# word_clock.net
KiCad netlist of a schematic drawn in EAGLE
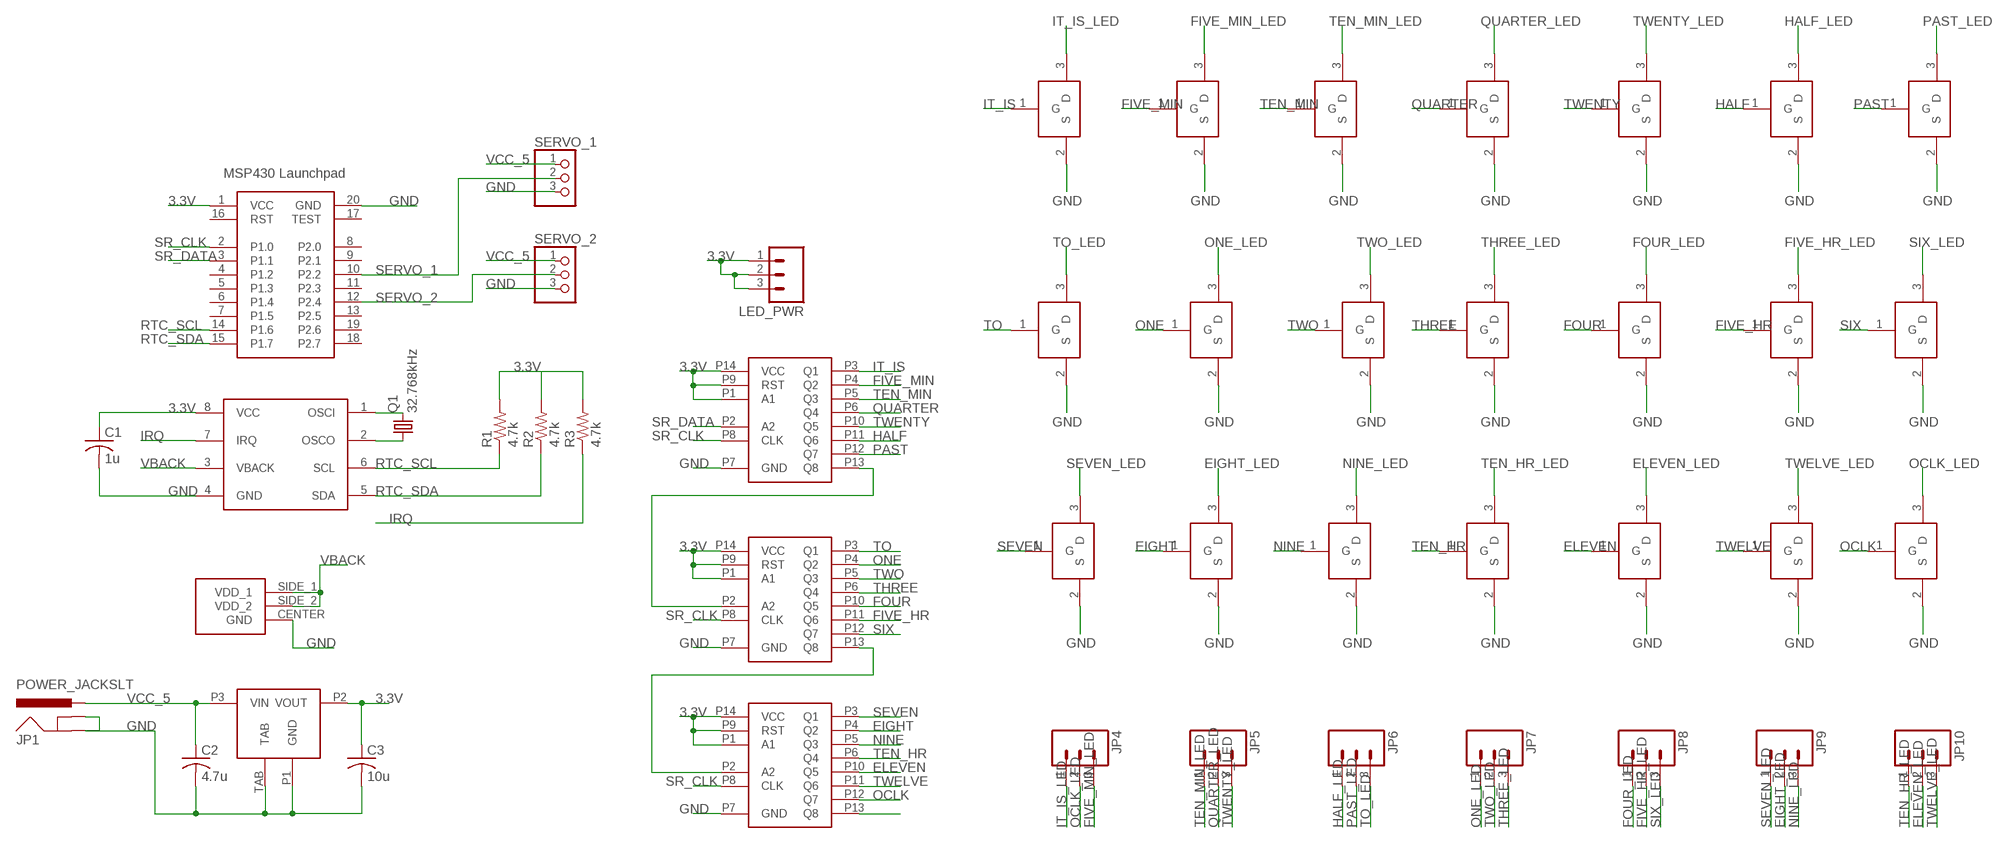
[diagram p0: schematic, sheet 1]

(export (version "E")
  (design (tool "Eeschema 10.0.6"))
  (components
    (comp (ref "1H")
      (value "FET")
      (footprint "eagle-import:SOT23")
      (libsource (lib "eagle-import") (part "FET"))
    )
    (comp (ref "2H")
      (value "FET")
      (footprint "eagle-import:SOT23")
      (libsource (lib "eagle-import") (part "FET"))
    )
    (comp (ref "3H")
      (value "FET")
      (footprint "eagle-import:SOT23")
      (libsource (lib "eagle-import") (part "FET"))
    )
    (comp (ref "4H")
      (value "FET")
      (footprint "eagle-import:SOT23")
      (libsource (lib "eagle-import") (part "FET"))
    )
    (comp (ref "5H")
      (value "FET")
      (footprint "eagle-import:SOT23")
      (libsource (lib "eagle-import") (part "FET"))
    )
    (comp (ref "5M")
      (value "FET")
      (footprint "eagle-import:SOT23")
      (libsource (lib "eagle-import") (part "FET"))
    )
    (comp (ref "6H")
      (value "FET")
      (footprint "eagle-import:SOT23")
      (libsource (lib "eagle-import") (part "FET"))
    )
    (comp (ref "7H")
      (value "FET")
      (footprint "eagle-import:SOT23")
      (libsource (lib "eagle-import") (part "FET"))
    )
    (comp (ref "8H")
      (value "FET")
      (footprint "eagle-import:SOT23")
      (libsource (lib "eagle-import") (part "FET"))
    )
    (comp (ref "9H")
      (value "FET")
      (footprint "eagle-import:SOT23")
      (libsource (lib "eagle-import") (part "FET"))
    )
    (comp (ref "10H")
      (value "FET")
      (footprint "eagle-import:SOT23")
      (libsource (lib "eagle-import") (part "FET"))
    )
    (comp (ref "10M")
      (value "FET")
      (footprint "eagle-import:SOT23")
      (libsource (lib "eagle-import") (part "FET"))
    )
    (comp (ref "11H")
      (value "FET")
      (footprint "eagle-import:SOT23")
      (libsource (lib "eagle-import") (part "FET"))
    )
    (comp (ref "12H")
      (value "FET")
      (footprint "eagle-import:SOT23")
      (libsource (lib "eagle-import") (part "FET"))
    )
    (comp (ref "15M")
      (value "FET")
      (footprint "eagle-import:SOT23")
      (libsource (lib "eagle-import") (part "FET"))
    )
    (comp (ref "20M")
      (value "FET")
      (footprint "eagle-import:SOT23")
      (libsource (lib "eagle-import") (part "FET"))
    )
    (comp (ref "30M")
      (value "FET")
      (footprint "eagle-import:SOT23")
      (libsource (lib "eagle-import") (part "FET"))
    )
    (comp (ref "C1")
      (value "1u")
      (footprint "eagle-import:C050-025X075")
      (libsource (lib "eagle-import") (part "C-US050-025X075"))
    )
    (comp (ref "C2")
      (value "4.7u")
      (footprint "eagle-import:C050-025X075")
      (libsource (lib "eagle-import") (part "C-US050-025X075"))
    )
    (comp (ref "C3")
      (value "10u")
      (footprint "eagle-import:C050-025X075")
      (libsource (lib "eagle-import") (part "C-US050-025X075"))
    )
    (comp (ref "ITIS")
      (value "FET")
      (footprint "eagle-import:SOT23")
      (libsource (lib "eagle-import") (part "FET"))
    )
    (comp (ref "JP1")
      (value "POWER_JACKSLT")
      (footprint "eagle-import:POWER_JACK_SLOT")
      (libsource (lib "eagle-import") (part "POWER_JACKSLT"))
    )
    (comp (ref "JP4")
      (value "M03-SCREW-5MM")
      (footprint "eagle-import:SCREWTERMINAL-5MM-3")
      (libsource (lib "eagle-import") (part "M03-SCREW-5MM"))
    )
    (comp (ref "JP5")
      (value "M03-SCREW-5MM")
      (footprint "eagle-import:SCREWTERMINAL-5MM-3")
      (libsource (lib "eagle-import") (part "M03-SCREW-5MM"))
    )
    (comp (ref "JP6")
      (value "M03-SCREW-5MM")
      (footprint "eagle-import:SCREWTERMINAL-5MM-3")
      (libsource (lib "eagle-import") (part "M03-SCREW-5MM"))
    )
    (comp (ref "JP7")
      (value "M03-SCREW-5MM")
      (footprint "eagle-import:SCREWTERMINAL-5MM-3")
      (libsource (lib "eagle-import") (part "M03-SCREW-5MM"))
    )
    (comp (ref "JP8")
      (value "M03-SCREW-5MM")
      (footprint "eagle-import:SCREWTERMINAL-5MM-3")
      (libsource (lib "eagle-import") (part "M03-SCREW-5MM"))
    )
    (comp (ref "JP9")
      (value "M03-SCREW-5MM")
      (footprint "eagle-import:SCREWTERMINAL-5MM-3")
      (libsource (lib "eagle-import") (part "M03-SCREW-5MM"))
    )
    (comp (ref "JP10")
      (value "M03-SCREW-5MM")
      (footprint "eagle-import:SCREWTERMINAL-5MM-3")
      (libsource (lib "eagle-import") (part "M03-SCREW-5MM"))
    )
    (comp (ref "LED_PWR")
      (value "M03-SCREW-5MM")
      (footprint "eagle-import:SCREWTERMINAL-5MM-3")
      (libsource (lib "eagle-import") (part "M03-SCREW-5MM"))
    )
    (comp (ref "OCLK")
      (value "FET")
      (footprint "eagle-import:SOT23")
      (libsource (lib "eagle-import") (part "FET"))
    )
    (comp (ref "PAST")
      (value "FET")
      (footprint "eagle-import:SOT23")
      (libsource (lib "eagle-import") (part "FET"))
    )
    (comp (ref "Q1")
      (value "32.768kHz")
      (footprint "eagle-import:TC26V")
      (libsource (lib "eagle-import") (part "CRYSTALTC26V"))
    )
    (comp (ref "R1")
      (value "4.7k")
      (footprint "eagle-import:0207_10")
      (libsource (lib "eagle-import") (part "R-US_0207/10"))
    )
    (comp (ref "R2")
      (value "4.7k")
      (footprint "eagle-import:0207_10")
      (libsource (lib "eagle-import") (part "R-US_0207/10"))
    )
    (comp (ref "R3")
      (value "4.7k")
      (footprint "eagle-import:0207_10")
      (libsource (lib "eagle-import") (part "R-US_0207/10"))
    )
    (comp (ref "RTC")
      (value "RTC")
      (footprint "eagle-import:SOIC8")
      (libsource (lib "eagle-import") (part "RTC"))
    )
    (comp (ref "SERVO_1")
      (value "PINHD-1X3")
      (footprint "eagle-import:1X03")
      (libsource (lib "eagle-import") (part "PINHD-1X3"))
    )
    (comp (ref "SERVO_2")
      (value "PINHD-1X3")
      (footprint "eagle-import:1X03")
      (libsource (lib "eagle-import") (part "PINHD-1X3"))
    )
    (comp (ref "SR_1")
      (value "SHIFT_REGISTER")
      (footprint "eagle-import:SHIFT_REGISTER")
      (libsource (lib "eagle-import") (part "SHIFT_REGISTER"))
    )
    (comp (ref "SR_2")
      (value "SHIFT_REGISTER")
      (footprint "eagle-import:SHIFT_REGISTER")
      (libsource (lib "eagle-import") (part "SHIFT_REGISTER"))
    )
    (comp (ref "TO")
      (value "FET")
      (footprint "eagle-import:SOT23")
      (libsource (lib "eagle-import") (part "FET"))
    )
    (comp (ref "U$1")
      (value "SHIFT_REGISTER")
      (footprint "eagle-import:SHIFT_REGISTER")
      (libsource (lib "eagle-import") (part "SHIFT_REGISTER"))
    )
    (comp (ref "U$4")
      (value "LDO")
      (footprint "eagle-import:LDO")
      (libsource (lib "eagle-import") (part "LDO"))
    )
    (comp (ref "U$25")
      (value "MSP430")
      (footprint "eagle-import:MSP430")
      (libsource (lib "eagle-import") (part "MSP430"))
    )
    (comp (ref "U$28")
      (value "COIN_CELL_SPARKFUN")
      (footprint "eagle-import:COIN_CELL_SPARKFUN")
      (libsource (lib "eagle-import") (part "COIN_CELL_SPARKFUN"))
    )
  )
  (nets
    (net (code "1") (name "/3.3V") (class "Default")
      (node (ref "C1") (pin "1") (pinfunction "1_1") (pintype "passive"))
      (node (ref "C3") (pin "1") (pinfunction "1_1") (pintype "passive"))
      (node (ref "LED_PWR") (pin "1") (pinfunction "1_1") (pintype "passive"))
      (node (ref "LED_PWR") (pin "2") (pinfunction "2_2") (pintype "passive"))
      (node (ref "LED_PWR") (pin "3") (pinfunction "3_3") (pintype "passive"))
      (node (ref "R1") (pin "2") (pinfunction "2_2") (pintype "passive"))
      (node (ref "R2") (pin "2") (pinfunction "2_2") (pintype "passive"))
      (node (ref "R3") (pin "2") (pinfunction "2_2") (pintype "passive"))
      (node (ref "RTC") (pin "8") (pinfunction "VCC_8") (pintype "bidirectional"))
      (node (ref "SR_1") (pin "P1") (pinfunction "A1_P1") (pintype "bidirectional"))
      (node (ref "SR_1") (pin "P14") (pinfunction "VCC_P14") (pintype "bidirectional"))
      (node (ref "SR_1") (pin "P9") (pinfunction "RST_P9") (pintype "bidirectional"))
      (node (ref "SR_2") (pin "P1") (pinfunction "A1_P1") (pintype "bidirectional"))
      (node (ref "SR_2") (pin "P14") (pinfunction "VCC_P14") (pintype "bidirectional"))
      (node (ref "SR_2") (pin "P9") (pinfunction "RST_P9") (pintype "bidirectional"))
      (node (ref "U$1") (pin "P1") (pinfunction "A1_P1") (pintype "bidirectional"))
      (node (ref "U$1") (pin "P14") (pinfunction "VCC_P14") (pintype "bidirectional"))
      (node (ref "U$1") (pin "P9") (pinfunction "RST_P9") (pintype "bidirectional"))
      (node (ref "U$25") (pin "1") (pinfunction "VCC_1") (pintype "bidirectional"))
      (node (ref "U$4") (pin "P2") (pinfunction "VOUT_P2") (pintype "bidirectional"))
    )
    (net (code "2") (name "/EIGHT") (class "Default")
      (node (ref "8H") (pin "1") (pinfunction "G_1") (pintype "bidirectional"))
      (node (ref "U$1") (pin "P4") (pinfunction "Q2_P4") (pintype "bidirectional"))
    )
    (net (code "3") (name "/EIGHT_LED") (class "Default")
      (node (ref "8H") (pin "3") (pinfunction "D_3") (pintype "bidirectional"))
      (node (ref "JP9") (pin "2") (pinfunction "2_2") (pintype "passive"))
    )
    (net (code "4") (name "/ELEVEN") (class "Default")
      (node (ref "11H") (pin "1") (pinfunction "G_1") (pintype "bidirectional"))
      (node (ref "U$1") (pin "P10") (pinfunction "Q5_P10") (pintype "bidirectional"))
    )
    (net (code "5") (name "/ELEVEN_LED") (class "Default")
      (node (ref "11H") (pin "3") (pinfunction "D_3") (pintype "bidirectional"))
      (node (ref "JP10") (pin "2") (pinfunction "2_2") (pintype "passive"))
    )
    (net (code "6") (name "/FIVE_HR") (class "Default")
      (node (ref "5H") (pin "1") (pinfunction "G_1") (pintype "bidirectional"))
      (node (ref "SR_2") (pin "P11") (pinfunction "Q6_P11") (pintype "bidirectional"))
    )
    (net (code "7") (name "/FIVE_HR_LED") (class "Default")
      (node (ref "5H") (pin "3") (pinfunction "D_3") (pintype "bidirectional"))
      (node (ref "JP8") (pin "2") (pinfunction "2_2") (pintype "passive"))
    )
    (net (code "8") (name "/FIVE_MIN") (class "Default")
      (node (ref "5M") (pin "1") (pinfunction "G_1") (pintype "bidirectional"))
      (node (ref "SR_1") (pin "P4") (pinfunction "Q2_P4") (pintype "bidirectional"))
    )
    (net (code "9") (name "/FIVE_MIN_LED") (class "Default")
      (node (ref "5M") (pin "3") (pinfunction "D_3") (pintype "bidirectional"))
      (node (ref "JP4") (pin "3") (pinfunction "3_3") (pintype "passive"))
    )
    (net (code "10") (name "/FOUR") (class "Default")
      (node (ref "4H") (pin "1") (pinfunction "G_1") (pintype "bidirectional"))
      (node (ref "SR_2") (pin "P10") (pinfunction "Q5_P10") (pintype "bidirectional"))
    )
    (net (code "11") (name "/FOUR_LED") (class "Default")
      (node (ref "4H") (pin "3") (pinfunction "D_3") (pintype "bidirectional"))
      (node (ref "JP8") (pin "1") (pinfunction "1_1") (pintype "passive"))
    )
    (net (code "12") (name "/GND") (class "Default")
      (node (ref "10H") (pin "2") (pinfunction "S_2") (pintype "bidirectional"))
      (node (ref "10M") (pin "2") (pinfunction "S_2") (pintype "bidirectional"))
      (node (ref "11H") (pin "2") (pinfunction "S_2") (pintype "bidirectional"))
      (node (ref "12H") (pin "2") (pinfunction "S_2") (pintype "bidirectional"))
      (node (ref "15M") (pin "2") (pinfunction "S_2") (pintype "bidirectional"))
      (node (ref "1H") (pin "2") (pinfunction "S_2") (pintype "bidirectional"))
      (node (ref "20M") (pin "2") (pinfunction "S_2") (pintype "bidirectional"))
      (node (ref "2H") (pin "2") (pinfunction "S_2") (pintype "bidirectional"))
      (node (ref "30M") (pin "2") (pinfunction "S_2") (pintype "bidirectional"))
      (node (ref "3H") (pin "2") (pinfunction "S_2") (pintype "bidirectional"))
      (node (ref "4H") (pin "2") (pinfunction "S_2") (pintype "bidirectional"))
      (node (ref "5H") (pin "2") (pinfunction "S_2") (pintype "bidirectional"))
      (node (ref "5M") (pin "2") (pinfunction "S_2") (pintype "bidirectional"))
      (node (ref "6H") (pin "2") (pinfunction "S_2") (pintype "bidirectional"))
      (node (ref "7H") (pin "2") (pinfunction "S_2") (pintype "bidirectional"))
      (node (ref "8H") (pin "2") (pinfunction "S_2") (pintype "bidirectional"))
      (node (ref "9H") (pin "2") (pinfunction "S_2") (pintype "bidirectional"))
      (node (ref "C1") (pin "2") (pinfunction "2_2") (pintype "passive"))
      (node (ref "C2") (pin "2") (pinfunction "2_2") (pintype "passive"))
      (node (ref "C3") (pin "2") (pinfunction "2_2") (pintype "passive"))
      (node (ref "ITIS") (pin "2") (pinfunction "S_2") (pintype "bidirectional"))
      (node (ref "JP1") (pin "GND@1") (pinfunction "GNDBREAK_GND@1") (pintype "bidirectional"))
      (node (ref "JP1") (pin "GND@2") (pinfunction "GND_GND@2") (pintype "bidirectional"))
      (node (ref "OCLK") (pin "2") (pinfunction "S_2") (pintype "bidirectional"))
      (node (ref "PAST") (pin "2") (pinfunction "S_2") (pintype "bidirectional"))
      (node (ref "RTC") (pin "4") (pinfunction "GND_4") (pintype "bidirectional"))
      (node (ref "SERVO_1") (pin "3") (pinfunction "3_3") (pintype "passive"))
      (node (ref "SERVO_2") (pin "3") (pinfunction "3_3") (pintype "passive"))
      (node (ref "SR_1") (pin "P7") (pinfunction "GND_P7") (pintype "bidirectional"))
      (node (ref "SR_2") (pin "P7") (pinfunction "GND_P7") (pintype "bidirectional"))
      (node (ref "TO") (pin "2") (pinfunction "S_2") (pintype "bidirectional"))
      (node (ref "U$1") (pin "P7") (pinfunction "GND_P7") (pintype "bidirectional"))
      (node (ref "U$25") (pin "20") (pinfunction "GND_20") (pintype "bidirectional"))
      (node (ref "U$28") (pin "CENTER") (pinfunction "GND_CENTER") (pintype "bidirectional"))
      (node (ref "U$4") (pin "P1") (pinfunction "GND_P1") (pintype "bidirectional"))
      (node (ref "U$4") (pin "TAB") (pinfunction "TAB_TAB") (pintype "bidirectional"))
    )
    (net (code "13") (name "/HALF") (class "Default")
      (node (ref "30M") (pin "1") (pinfunction "G_1") (pintype "bidirectional"))
      (node (ref "SR_1") (pin "P11") (pinfunction "Q6_P11") (pintype "bidirectional"))
    )
    (net (code "14") (name "/HALF_LED") (class "Default")
      (node (ref "30M") (pin "3") (pinfunction "D_3") (pintype "bidirectional"))
      (node (ref "JP6") (pin "1") (pinfunction "1_1") (pintype "passive"))
    )
    (net (code "15") (name "/IRQ") (class "Default")
      (node (ref "R3") (pin "1") (pinfunction "1_1") (pintype "passive"))
      (node (ref "RTC") (pin "7") (pinfunction "IRQ_7") (pintype "bidirectional"))
    )
    (net (code "16") (name "/IT_IS") (class "Default")
      (node (ref "ITIS") (pin "1") (pinfunction "G_1") (pintype "bidirectional"))
      (node (ref "SR_1") (pin "P3") (pinfunction "Q1_P3") (pintype "bidirectional"))
    )
    (net (code "17") (name "/IT_IS_LED") (class "Default")
      (node (ref "ITIS") (pin "3") (pinfunction "D_3") (pintype "bidirectional"))
      (node (ref "JP4") (pin "1") (pinfunction "1_1") (pintype "passive"))
    )
    (net (code "18") (name "/NINE") (class "Default")
      (node (ref "9H") (pin "1") (pinfunction "G_1") (pintype "bidirectional"))
      (node (ref "U$1") (pin "P5") (pinfunction "Q3_P5") (pintype "bidirectional"))
    )
    (net (code "19") (name "/NINE_LED") (class "Default")
      (node (ref "9H") (pin "3") (pinfunction "D_3") (pintype "bidirectional"))
      (node (ref "JP9") (pin "3") (pinfunction "3_3") (pintype "passive"))
    )
    (net (code "20") (name "/OCLK") (class "Default")
      (node (ref "OCLK") (pin "1") (pinfunction "G_1") (pintype "bidirectional"))
      (node (ref "U$1") (pin "P12") (pinfunction "Q7_P12") (pintype "bidirectional"))
    )
    (net (code "21") (name "/OCLK_LED") (class "Default")
      (node (ref "JP4") (pin "2") (pinfunction "2_2") (pintype "passive"))
      (node (ref "OCLK") (pin "3") (pinfunction "D_3") (pintype "bidirectional"))
    )
    (net (code "22") (name "/ONE") (class "Default")
      (node (ref "1H") (pin "1") (pinfunction "G_1") (pintype "bidirectional"))
      (node (ref "SR_2") (pin "P4") (pinfunction "Q2_P4") (pintype "bidirectional"))
    )
    (net (code "23") (name "/ONE_LED") (class "Default")
      (node (ref "1H") (pin "3") (pinfunction "D_3") (pintype "bidirectional"))
      (node (ref "JP7") (pin "1") (pinfunction "1_1") (pintype "passive"))
    )
    (net (code "24") (name "/PAST") (class "Default")
      (node (ref "PAST") (pin "1") (pinfunction "G_1") (pintype "bidirectional"))
      (node (ref "SR_1") (pin "P12") (pinfunction "Q7_P12") (pintype "bidirectional"))
    )
    (net (code "25") (name "/PAST_LED") (class "Default")
      (node (ref "JP6") (pin "2") (pinfunction "2_2") (pintype "passive"))
      (node (ref "PAST") (pin "3") (pinfunction "D_3") (pintype "bidirectional"))
    )
    (net (code "26") (name "/QUARTER") (class "Default")
      (node (ref "15M") (pin "1") (pinfunction "G_1") (pintype "bidirectional"))
      (node (ref "SR_1") (pin "P6") (pinfunction "Q4_P6") (pintype "bidirectional"))
    )
    (net (code "27") (name "/QUARTER_LED") (class "Default")
      (node (ref "15M") (pin "3") (pinfunction "D_3") (pintype "bidirectional"))
      (node (ref "JP5") (pin "2") (pinfunction "2_2") (pintype "passive"))
    )
    (net (code "28") (name "/RTC_SCL") (class "Default")
      (node (ref "R1") (pin "1") (pinfunction "1_1") (pintype "passive"))
      (node (ref "RTC") (pin "6") (pinfunction "SCL_6") (pintype "bidirectional"))
      (node (ref "U$25") (pin "14") (pinfunction "P1.6_14") (pintype "bidirectional"))
    )
    (net (code "29") (name "/RTC_SDA") (class "Default")
      (node (ref "R2") (pin "1") (pinfunction "1_1") (pintype "passive"))
      (node (ref "RTC") (pin "5") (pinfunction "SDA_5") (pintype "bidirectional"))
      (node (ref "U$25") (pin "15") (pinfunction "P1.7_15") (pintype "bidirectional"))
    )
    (net (code "30") (name "/SERVO_1") (class "Default")
      (node (ref "SERVO_1") (pin "2") (pinfunction "2_2") (pintype "passive"))
      (node (ref "U$25") (pin "10") (pinfunction "P2.2_10") (pintype "bidirectional"))
    )
    (net (code "31") (name "/SERVO_2") (class "Default")
      (node (ref "SERVO_2") (pin "2") (pinfunction "2_2") (pintype "passive"))
      (node (ref "U$25") (pin "12") (pinfunction "P2.4_12") (pintype "bidirectional"))
    )
    (net (code "32") (name "/SEVEN") (class "Default")
      (node (ref "7H") (pin "1") (pinfunction "G_1") (pintype "bidirectional"))
      (node (ref "U$1") (pin "P3") (pinfunction "Q1_P3") (pintype "bidirectional"))
    )
    (net (code "33") (name "/SEVEN_LED") (class "Default")
      (node (ref "7H") (pin "3") (pinfunction "D_3") (pintype "bidirectional"))
      (node (ref "JP9") (pin "1") (pinfunction "1_1") (pintype "passive"))
    )
    (net (code "34") (name "/SIX") (class "Default")
      (node (ref "6H") (pin "1") (pinfunction "G_1") (pintype "bidirectional"))
      (node (ref "SR_2") (pin "P12") (pinfunction "Q7_P12") (pintype "bidirectional"))
    )
    (net (code "35") (name "/SIX_LED") (class "Default")
      (node (ref "6H") (pin "3") (pinfunction "D_3") (pintype "bidirectional"))
      (node (ref "JP8") (pin "3") (pinfunction "3_3") (pintype "passive"))
    )
    (net (code "36") (name "/SR_CLK") (class "Default")
      (node (ref "SR_1") (pin "P8") (pinfunction "CLK_P8") (pintype "bidirectional"))
      (node (ref "SR_2") (pin "P8") (pinfunction "CLK_P8") (pintype "bidirectional"))
      (node (ref "U$1") (pin "P8") (pinfunction "CLK_P8") (pintype "bidirectional"))
      (node (ref "U$25") (pin "2") (pinfunction "P1.0_2") (pintype "bidirectional"))
    )
    (net (code "37") (name "/SR_DATA") (class "Default")
      (node (ref "SR_1") (pin "P2") (pinfunction "A2_P2") (pintype "bidirectional"))
      (node (ref "U$25") (pin "3") (pinfunction "P1.1_3") (pintype "bidirectional"))
    )
    (net (code "38") (name "/TEN_HR") (class "Default")
      (node (ref "10H") (pin "1") (pinfunction "G_1") (pintype "bidirectional"))
      (node (ref "U$1") (pin "P6") (pinfunction "Q4_P6") (pintype "bidirectional"))
    )
    (net (code "39") (name "/TEN_HR_LED") (class "Default")
      (node (ref "10H") (pin "3") (pinfunction "D_3") (pintype "bidirectional"))
      (node (ref "JP10") (pin "1") (pinfunction "1_1") (pintype "passive"))
    )
    (net (code "40") (name "/TEN_MIN") (class "Default")
      (node (ref "10M") (pin "1") (pinfunction "G_1") (pintype "bidirectional"))
      (node (ref "SR_1") (pin "P5") (pinfunction "Q3_P5") (pintype "bidirectional"))
    )
    (net (code "41") (name "/TEN_MIN_LED") (class "Default")
      (node (ref "10M") (pin "3") (pinfunction "D_3") (pintype "bidirectional"))
      (node (ref "JP5") (pin "1") (pinfunction "1_1") (pintype "passive"))
    )
    (net (code "42") (name "/THREE") (class "Default")
      (node (ref "3H") (pin "1") (pinfunction "G_1") (pintype "bidirectional"))
      (node (ref "SR_2") (pin "P6") (pinfunction "Q4_P6") (pintype "bidirectional"))
    )
    (net (code "43") (name "/THREE_LED") (class "Default")
      (node (ref "3H") (pin "3") (pinfunction "D_3") (pintype "bidirectional"))
      (node (ref "JP7") (pin "3") (pinfunction "3_3") (pintype "passive"))
    )
    (net (code "44") (name "/TO") (class "Default")
      (node (ref "SR_2") (pin "P3") (pinfunction "Q1_P3") (pintype "bidirectional"))
      (node (ref "TO") (pin "1") (pinfunction "G_1") (pintype "bidirectional"))
    )
    (net (code "45") (name "/TO_LED") (class "Default")
      (node (ref "JP6") (pin "3") (pinfunction "3_3") (pintype "passive"))
      (node (ref "TO") (pin "3") (pinfunction "D_3") (pintype "bidirectional"))
    )
    (net (code "46") (name "/TWELVE") (class "Default")
      (node (ref "12H") (pin "1") (pinfunction "G_1") (pintype "bidirectional"))
      (node (ref "U$1") (pin "P11") (pinfunction "Q6_P11") (pintype "bidirectional"))
    )
    (net (code "47") (name "/TWELVE_LED") (class "Default")
      (node (ref "12H") (pin "3") (pinfunction "D_3") (pintype "bidirectional"))
      (node (ref "JP10") (pin "3") (pinfunction "3_3") (pintype "passive"))
    )
    (net (code "48") (name "/TWENTY") (class "Default")
      (node (ref "20M") (pin "1") (pinfunction "G_1") (pintype "bidirectional"))
      (node (ref "SR_1") (pin "P10") (pinfunction "Q5_P10") (pintype "bidirectional"))
    )
    (net (code "49") (name "/TWENTY_LED") (class "Default")
      (node (ref "20M") (pin "3") (pinfunction "D_3") (pintype "bidirectional"))
      (node (ref "JP5") (pin "3") (pinfunction "3_3") (pintype "passive"))
    )
    (net (code "50") (name "/TWO") (class "Default")
      (node (ref "2H") (pin "1") (pinfunction "G_1") (pintype "bidirectional"))
      (node (ref "SR_2") (pin "P5") (pinfunction "Q3_P5") (pintype "bidirectional"))
    )
    (net (code "51") (name "/TWO_LED") (class "Default")
      (node (ref "2H") (pin "3") (pinfunction "D_3") (pintype "bidirectional"))
      (node (ref "JP7") (pin "2") (pinfunction "2_2") (pintype "passive"))
    )
    (net (code "52") (name "/VBACK") (class "Default")
      (node (ref "RTC") (pin "3") (pinfunction "VBACK_3") (pintype "bidirectional"))
      (node (ref "U$28") (pin "SIDE_1") (pinfunction "VDD_1_SIDE_1") (pintype "bidirectional"))
      (node (ref "U$28") (pin "SIDE_2") (pinfunction "VDD_2_SIDE_2") (pintype "bidirectional"))
    )
    (net (code "53") (name "/VCC_5") (class "Default")
      (node (ref "C2") (pin "1") (pinfunction "1_1") (pintype "passive"))
      (node (ref "JP1") (pin "PWR") (pinfunction "PWR_PWR") (pintype "bidirectional"))
      (node (ref "SERVO_1") (pin "1") (pinfunction "1_1") (pintype "passive"))
      (node (ref "SERVO_2") (pin "1") (pinfunction "1_1") (pintype "passive"))
      (node (ref "U$4") (pin "P3") (pinfunction "VIN_P3") (pintype "bidirectional"))
    )
    (net (code "54") (name "Net-(RTC-OSCI)") (class "Default")
      (node (ref "Q1") (pin "2") (pinfunction "2_2") (pintype "passive"))
      (node (ref "RTC") (pin "1") (pinfunction "OSCI_1") (pintype "bidirectional"))
    )
    (net (code "55") (name "Net-(RTC-OSCO)") (class "Default")
      (node (ref "Q1") (pin "1") (pinfunction "1_1") (pintype "passive"))
      (node (ref "RTC") (pin "2") (pinfunction "OSCO_2") (pintype "bidirectional"))
    )
    (net (code "56") (name "Net-(SR_1-Q8)") (class "Default")
      (node (ref "SR_1") (pin "P13") (pinfunction "Q8_P13") (pintype "output"))
      (node (ref "SR_2") (pin "P2") (pinfunction "A2_P2") (pintype "bidirectional"))
    )
    (net (code "57") (name "Net-(SR_2-Q8)") (class "Default")
      (node (ref "SR_2") (pin "P13") (pinfunction "Q8_P13") (pintype "output"))
      (node (ref "U$1") (pin "P2") (pinfunction "A2_P2") (pintype "bidirectional"))
    )
    (net (code "58") (name "unconnected-(U$1-Q8-PadP13)") (class "Default")
      (node (ref "U$1") (pin "P13") (pinfunction "Q8_P13") (pintype "output"))
    )
    (net (code "59") (name "unconnected-(U$25-P1.2-Pad4)") (class "Default")
      (node (ref "U$25") (pin "4") (pinfunction "P1.2_4") (pintype "bidirectional"))
    )
    (net (code "60") (name "unconnected-(U$25-P1.3-Pad5)") (class "Default")
      (node (ref "U$25") (pin "5") (pinfunction "P1.3_5") (pintype "bidirectional"))
    )
    (net (code "61") (name "unconnected-(U$25-P1.4-Pad6)") (class "Default")
      (node (ref "U$25") (pin "6") (pinfunction "P1.4_6") (pintype "bidirectional"))
    )
    (net (code "62") (name "unconnected-(U$25-P1.5-Pad7)") (class "Default")
      (node (ref "U$25") (pin "7") (pinfunction "P1.5_7") (pintype "bidirectional"))
    )
    (net (code "63") (name "unconnected-(U$25-P2.0-Pad8)") (class "Default")
      (node (ref "U$25") (pin "8") (pinfunction "P2.0_8") (pintype "bidirectional"))
    )
    (net (code "64") (name "unconnected-(U$25-P2.1-Pad9)") (class "Default")
      (node (ref "U$25") (pin "9") (pinfunction "P2.1_9") (pintype "bidirectional"))
    )
    (net (code "65") (name "unconnected-(U$25-P2.3-Pad11)") (class "Default")
      (node (ref "U$25") (pin "11") (pinfunction "P2.3_11") (pintype "bidirectional"))
    )
    (net (code "66") (name "unconnected-(U$25-P2.5-Pad13)") (class "Default")
      (node (ref "U$25") (pin "13") (pinfunction "P2.5_13") (pintype "bidirectional"))
    )
    (net (code "67") (name "unconnected-(U$25-P2.6-Pad19)") (class "Default")
      (node (ref "U$25") (pin "19") (pinfunction "P2.6_19") (pintype "bidirectional"))
    )
    (net (code "68") (name "unconnected-(U$25-P2.7-Pad18)") (class "Default")
      (node (ref "U$25") (pin "18") (pinfunction "P2.7_18") (pintype "bidirectional"))
    )
    (net (code "69") (name "unconnected-(U$25-RST-Pad16)") (class "Default")
      (node (ref "U$25") (pin "16") (pinfunction "RST_16") (pintype "bidirectional"))
    )
    (net (code "70") (name "unconnected-(U$25-TEST-Pad17)") (class "Default")
      (node (ref "U$25") (pin "17") (pinfunction "TEST_17") (pintype "bidirectional"))
    )
  )
)
